# MinGo_V4_0.net
KiCad netlist of a schematic drawn in Altium Designer
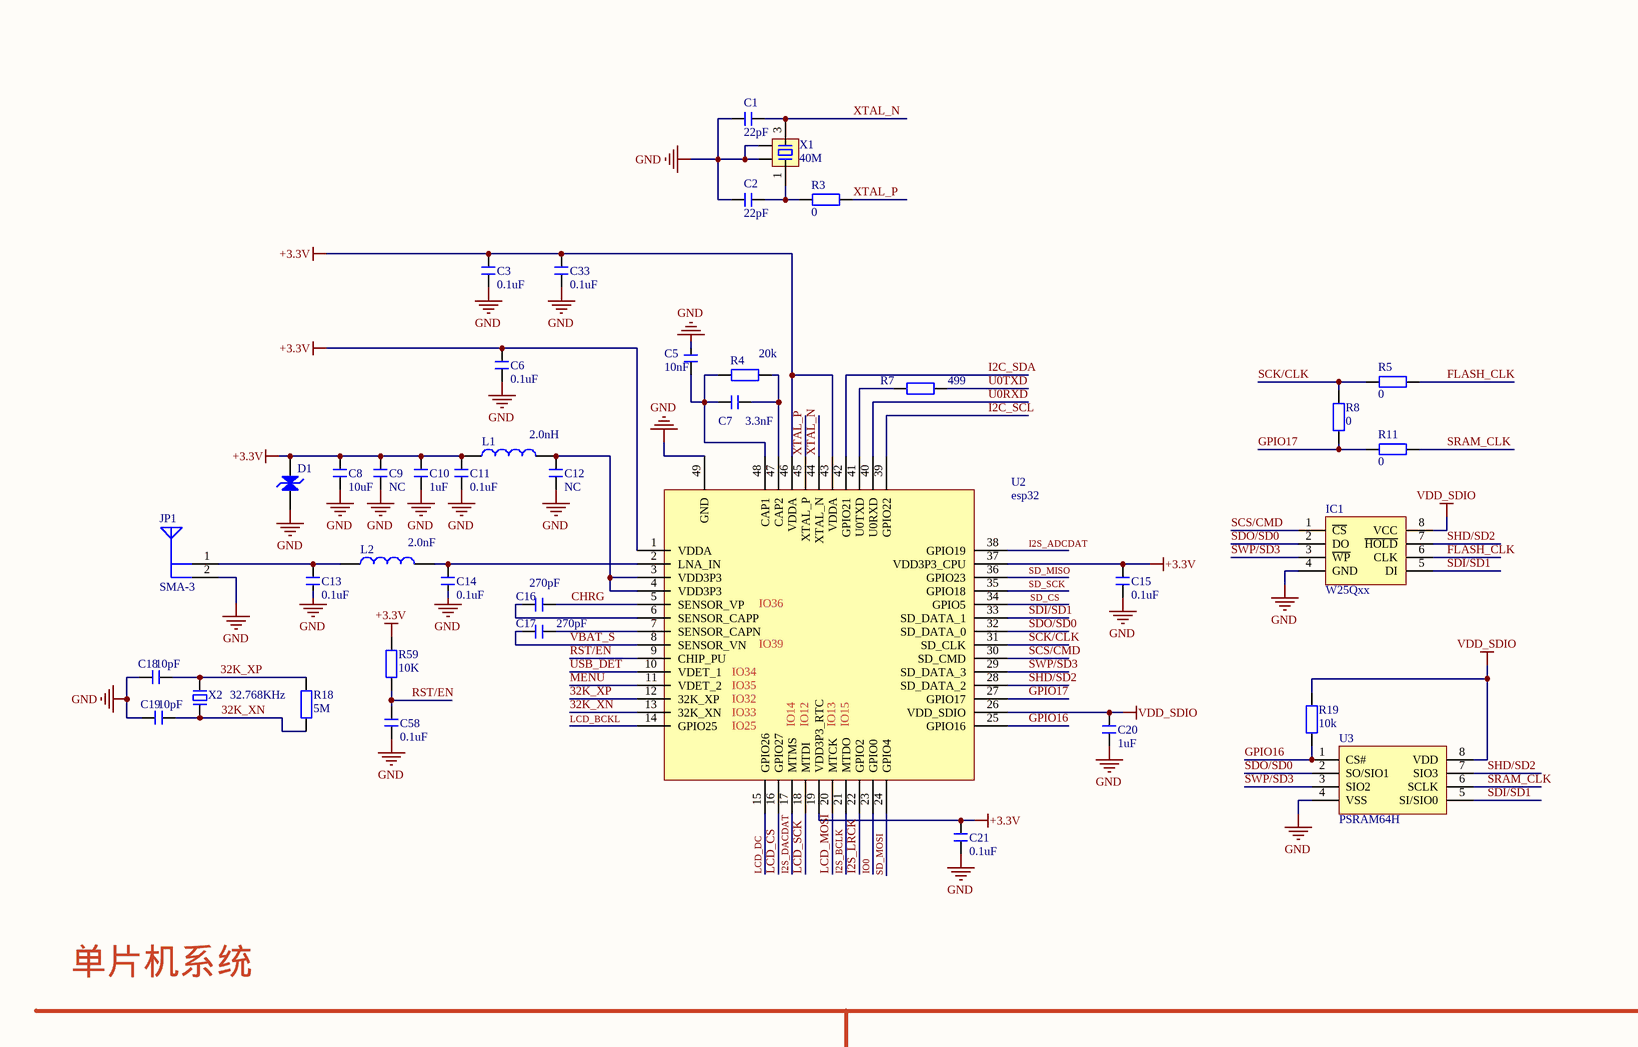
[diagram p0: MinGo_V4.0.SchDoc, top left]
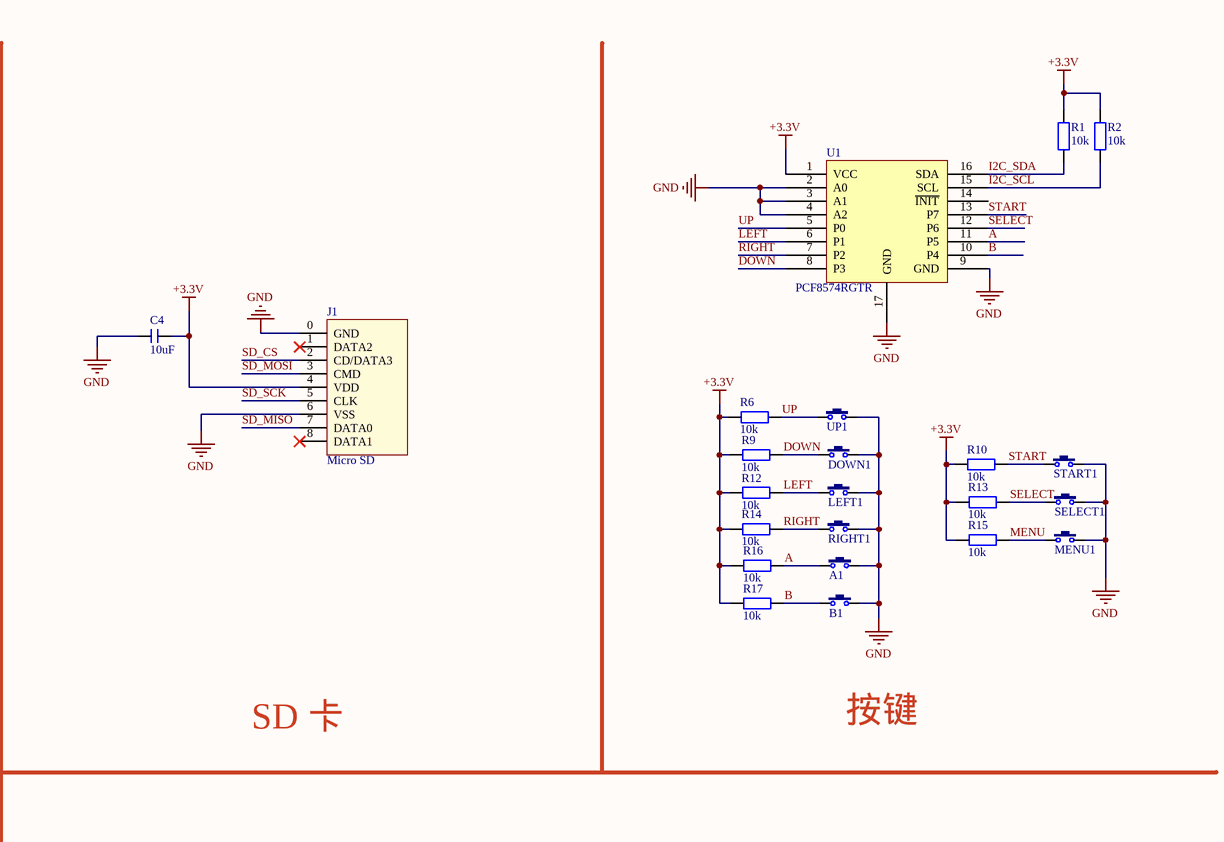
[diagram p1: MinGo_V4.0.SchDoc, top right]
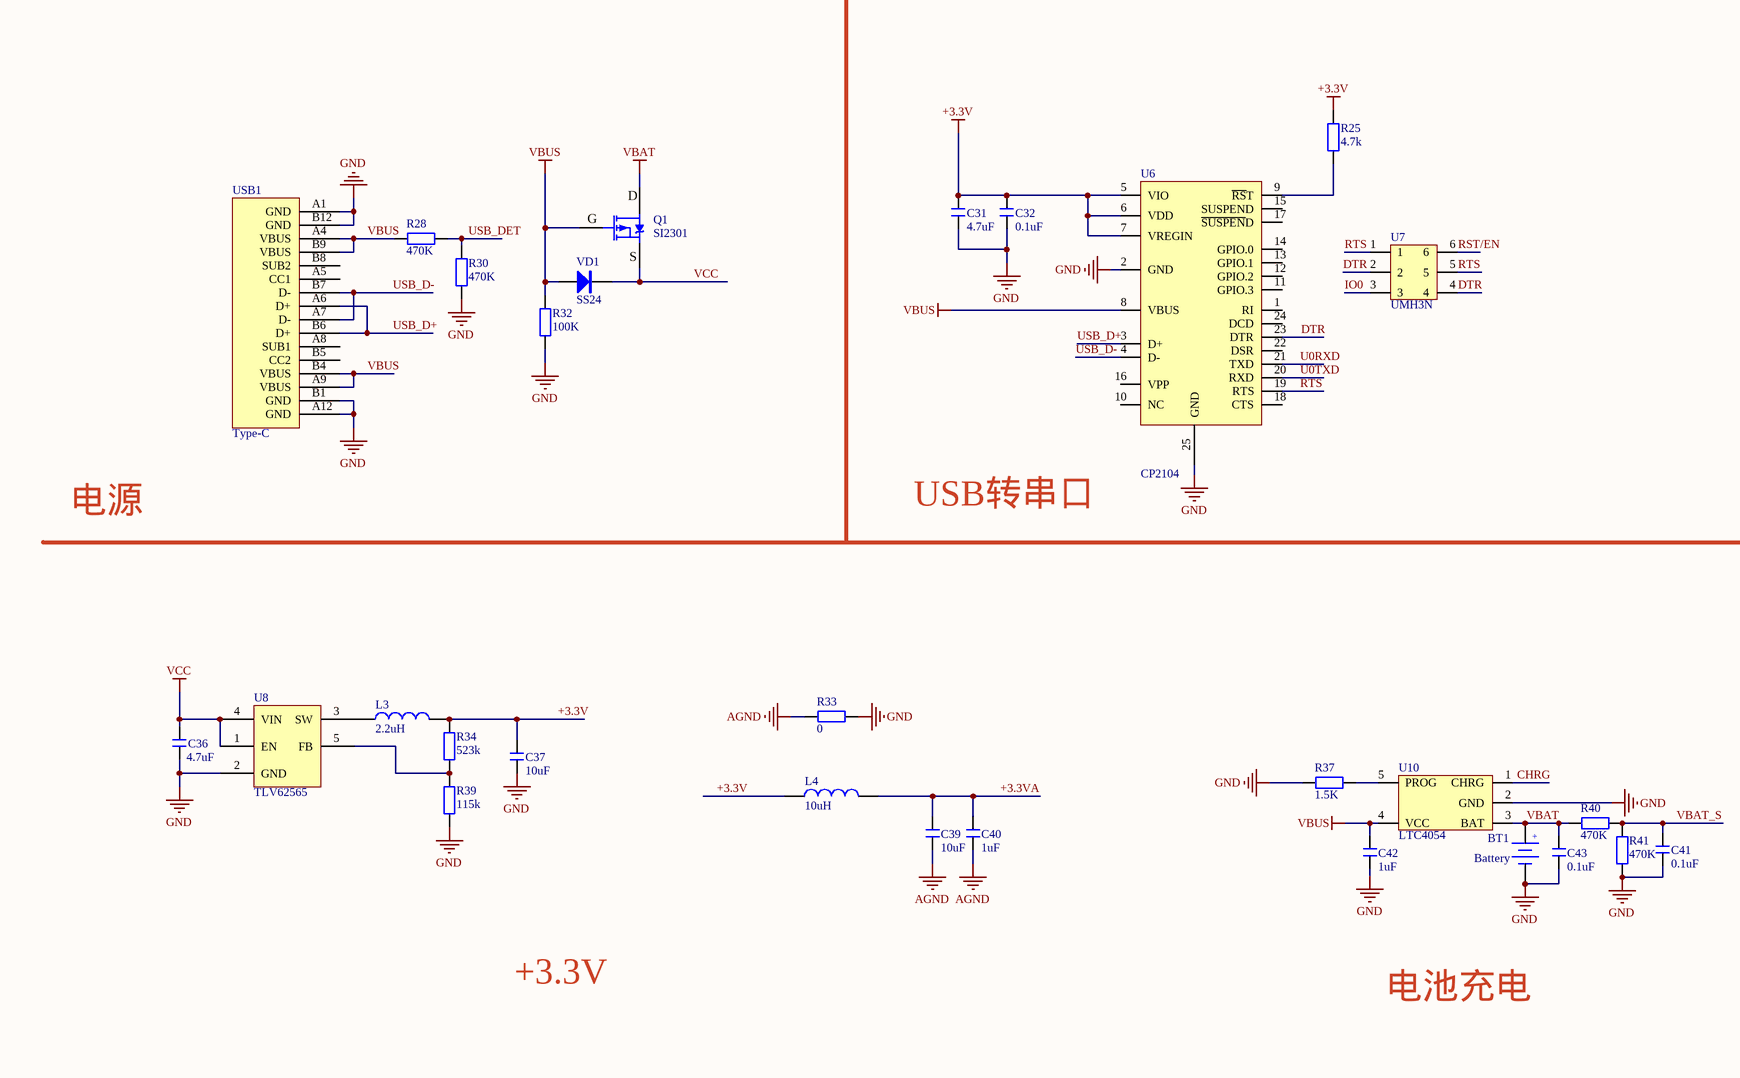
[diagram p2: MinGo_V4.0.SchDoc, bottom left]
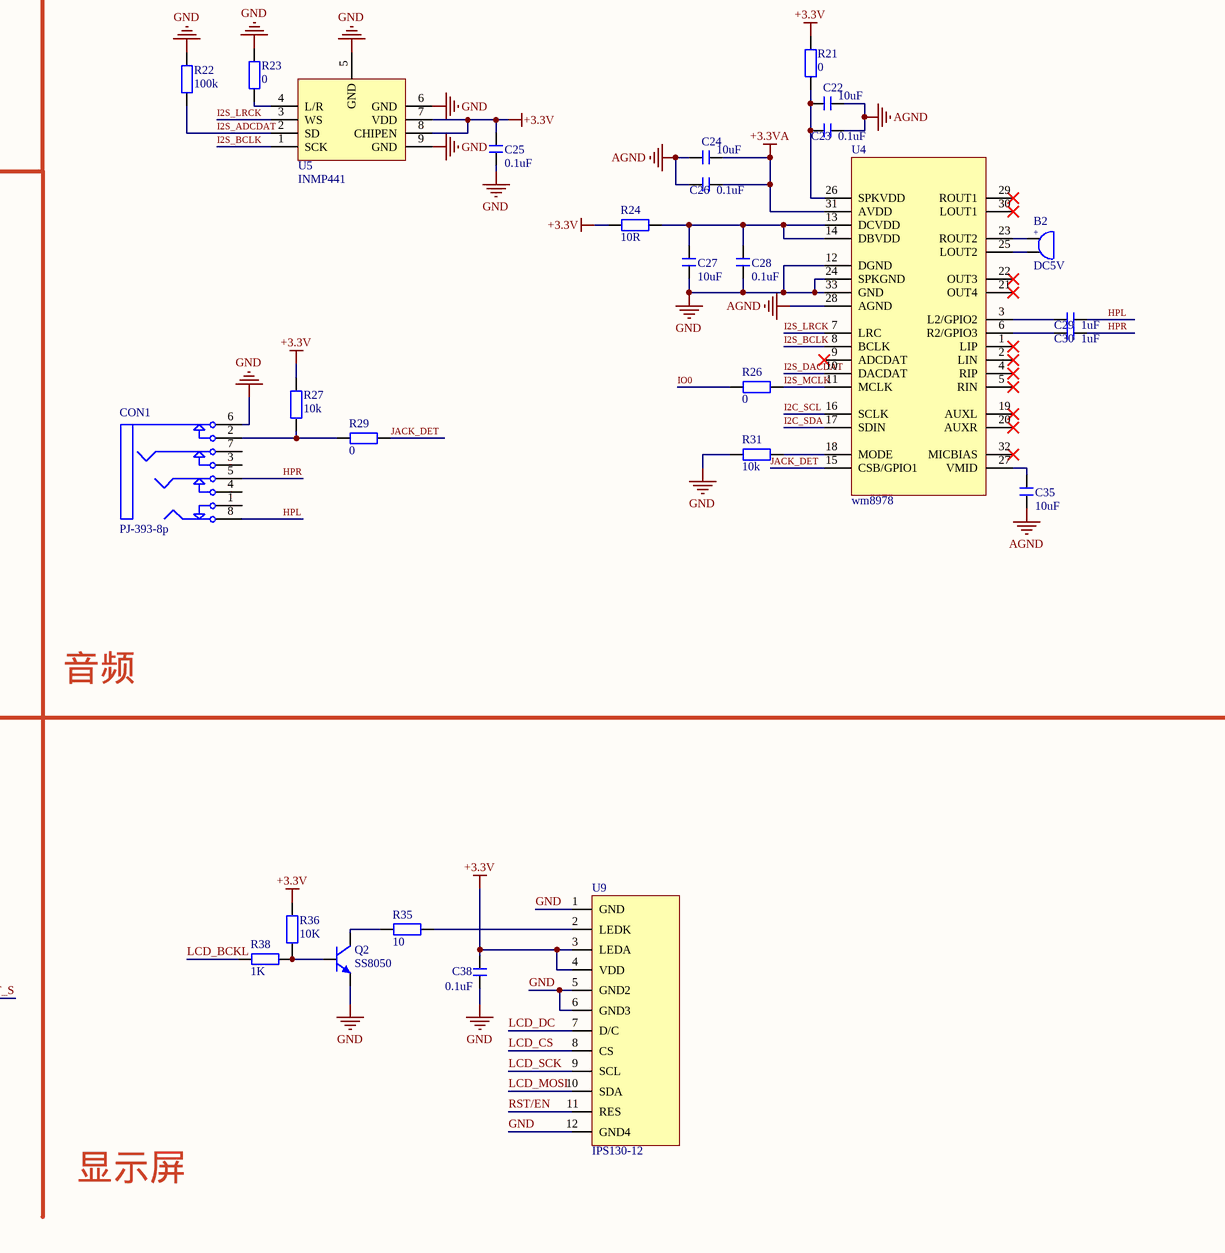
[diagram p3: MinGo_V4.0.SchDoc, bottom right]

(export (version "E")
  (design (tool "Eeschema 10.0.6"))
  (components
    (comp (ref "A1")
      (value "SW SMD-2")
      (footprint "Touch key 3")
      (description "Arduboy 用")
      (libsource (lib "按键-开关") (part "SW SMD-2"))
    )
    (comp (ref "B1")
      (value "SW SMD-2")
      (footprint "Touch key 3")
      (description "Arduboy 用")
      (libsource (lib "按键-开关") (part "SW SMD-2"))
    )
    (comp (ref "B2")
      (value "DC5V")
      (footprint "BEEP SMD-2")
      (description "蜂鸣器")
      (fields (field (name "版权归属") "黎明电子style"))
      (libsource (lib "未分类器件") (part "BEEP"))
    )
    (comp (ref "BT1")
      (value "Battery")
      (footprint "Li-Bettery SMD")
      (description "锂电池")
      (libsource (lib "未分类器件") (part "Battery"))
    )
    (comp (ref "C1")
      (value "22pF")
      (footprint "C 0402")
      (description "无极性贴片电容")
      (fields (field (name "版权归属") "黎明电子style"))
      (libsource (lib "电阻-电容-电感") (part "C"))
    )
    (comp (ref "C2")
      (value "22pF")
      (footprint "C 0402")
      (description "无极性贴片电容")
      (fields (field (name "版权归属") "黎明电子style"))
      (libsource (lib "电阻-电容-电感") (part "C"))
    )
    (comp (ref "C3")
      (value "0.1uF")
      (footprint "C 0402")
      (description "无极性贴片电容")
      (fields (field (name "版权归属") "黎明电子style"))
      (libsource (lib "电阻-电容-电感") (part "C"))
    )
    (comp (ref "C4")
      (value "10uF")
      (footprint "C 0603")
      (description "无极性贴片电容")
      (fields (field (name "版权归属") "黎明电子style"))
      (libsource (lib "电阻-电容-电感") (part "C"))
    )
    (comp (ref "C5")
      (value "10nF")
      (footprint "C 0402")
      (description "无极性贴片电容")
      (fields (field (name "版权归属") "黎明电子style"))
      (libsource (lib "电阻-电容-电感") (part "C"))
    )
    (comp (ref "C6")
      (value "0.1uF")
      (footprint "C 0402")
      (description "无极性贴片电容")
      (fields (field (name "版权归属") "黎明电子style"))
      (libsource (lib "电阻-电容-电感") (part "C"))
    )
    (comp (ref "C7")
      (value "3.3nF")
      (footprint "C 0402")
      (description "无极性贴片电容")
      (fields (field (name "版权归属") "黎明电子style"))
      (libsource (lib "电阻-电容-电感") (part "C"))
    )
    (comp (ref "C8")
      (value "10uF")
      (footprint "C 0603")
      (description "无极性贴片电容")
      (fields (field (name "版权归属") "黎明电子style"))
      (libsource (lib "电阻-电容-电感") (part "C"))
    )
    (comp (ref "C9")
      (value "NC")
      (footprint "C 0402")
      (description "无极性贴片电容")
      (fields (field (name "版权归属") "黎明电子style"))
      (libsource (lib "电阻-电容-电感") (part "C"))
    )
    (comp (ref "C10")
      (value "1uF")
      (footprint "C 0402")
      (description "无极性贴片电容")
      (fields (field (name "版权归属") "黎明电子style"))
      (libsource (lib "电阻-电容-电感") (part "C"))
    )
    (comp (ref "C11")
      (value "0.1uF")
      (footprint "C 0402")
      (description "无极性贴片电容")
      (fields (field (name "版权归属") "黎明电子style"))
      (libsource (lib "电阻-电容-电感") (part "C"))
    )
    (comp (ref "C12")
      (value "NC")
      (footprint "C 0402")
      (description "无极性贴片电容")
      (fields (field (name "版权归属") "黎明电子style"))
      (libsource (lib "电阻-电容-电感") (part "C"))
    )
    (comp (ref "C13")
      (value "0.1uF")
      (footprint "C 0402")
      (description "无极性贴片电容")
      (fields (field (name "版权归属") "黎明电子style"))
      (libsource (lib "电阻-电容-电感") (part "C"))
    )
    (comp (ref "C14")
      (value "0.1uF")
      (footprint "C 0402")
      (description "无极性贴片电容")
      (fields (field (name "版权归属") "黎明电子style"))
      (libsource (lib "电阻-电容-电感") (part "C"))
    )
    (comp (ref "C15")
      (value "0.1uF")
      (footprint "C 0402")
      (description "无极性贴片电容")
      (fields (field (name "版权归属") "黎明电子style"))
      (libsource (lib "电阻-电容-电感") (part "C"))
    )
    (comp (ref "C16")
      (value "270pF")
      (footprint "C 0402")
      (description "无极性贴片电容")
      (fields (field (name "版权归属") "黎明电子style"))
      (libsource (lib "电阻-电容-电感") (part "C"))
    )
    (comp (ref "C17")
      (value "270pF")
      (footprint "C 0402")
      (description "无极性贴片电容")
      (fields (field (name "版权归属") "黎明电子style"))
      (libsource (lib "电阻-电容-电感") (part "C"))
    )
    (comp (ref "C18")
      (value "10pF")
      (footprint "C 0402")
      (description "无极性贴片电容")
      (fields (field (name "版权归属") "黎明电子style"))
      (libsource (lib "电阻-电容-电感") (part "C"))
    )
    (comp (ref "C19")
      (value "10pF")
      (footprint "C 0402")
      (description "无极性贴片电容")
      (fields (field (name "版权归属") "黎明电子style"))
      (libsource (lib "电阻-电容-电感") (part "C"))
    )
    (comp (ref "C20")
      (value "1uF")
      (footprint "C 0402")
      (description "无极性贴片电容")
      (fields (field (name "版权归属") "黎明电子style"))
      (libsource (lib "电阻-电容-电感") (part "C"))
    )
    (comp (ref "C21")
      (value "0.1uF")
      (footprint "C 0402")
      (description "无极性贴片电容")
      (fields (field (name "版权归属") "黎明电子style"))
      (libsource (lib "电阻-电容-电感") (part "C"))
    )
    (comp (ref "C22")
      (value "10uF")
      (footprint "C 0603")
      (description "无极性贴片电容")
      (fields (field (name "版权归属") "黎明电子style"))
      (libsource (lib "电阻-电容-电感") (part "C"))
    )
    (comp (ref "C23")
      (value "0.1uF")
      (footprint "C 0402")
      (description "无极性贴片电容")
      (fields (field (name "版权归属") "黎明电子style"))
      (libsource (lib "电阻-电容-电感") (part "C"))
    )
    (comp (ref "C24")
      (value "10uF")
      (footprint "C 0603")
      (description "无极性贴片电容")
      (fields (field (name "版权归属") "黎明电子style"))
      (libsource (lib "电阻-电容-电感") (part "C"))
    )
    (comp (ref "C25")
      (value "0.1uF")
      (footprint "C 0402")
      (description "无极性贴片电容")
      (fields (field (name "版权归属") "黎明电子style"))
      (libsource (lib "电阻-电容-电感") (part "C"))
    )
    (comp (ref "C26")
      (value "0.1uF")
      (footprint "C 0402")
      (description "无极性贴片电容")
      (fields (field (name "版权归属") "黎明电子style"))
      (libsource (lib "电阻-电容-电感") (part "C"))
    )
    (comp (ref "C27")
      (value "10uF")
      (footprint "C 0603")
      (description "无极性贴片电容")
      (fields (field (name "版权归属") "黎明电子style"))
      (libsource (lib "电阻-电容-电感") (part "C"))
    )
    (comp (ref "C28")
      (value "0.1uF")
      (footprint "C 0402")
      (description "无极性贴片电容")
      (fields (field (name "版权归属") "黎明电子style"))
      (libsource (lib "电阻-电容-电感") (part "C"))
    )
    (comp (ref "C29")
      (value "1uF")
      (footprint "C 0603")
      (description "无极性贴片电容")
      (fields (field (name "版权归属") "黎明电子style"))
      (libsource (lib "电阻-电容-电感") (part "C"))
    )
    (comp (ref "C30")
      (value "1uF")
      (footprint "C 0603")
      (description "无极性贴片电容")
      (fields (field (name "版权归属") "黎明电子style"))
      (libsource (lib "电阻-电容-电感") (part "C"))
    )
    (comp (ref "C31")
      (value "4.7uF")
      (footprint "C 0603")
      (description "无极性贴片电容")
      (fields (field (name "版权归属") "黎明电子style"))
      (libsource (lib "电阻-电容-电感") (part "C"))
    )
    (comp (ref "C32")
      (value "0.1uF")
      (footprint "C 0402")
      (description "无极性贴片电容")
      (fields (field (name "版权归属") "黎明电子style"))
      (libsource (lib "电阻-电容-电感") (part "C"))
    )
    (comp (ref "C33")
      (value "0.1uF")
      (footprint "C 0402")
      (description "无极性贴片电容")
      (fields (field (name "版权归属") "黎明电子style"))
      (libsource (lib "电阻-电容-电感") (part "C"))
    )
    (comp (ref "C35")
      (value "10uF")
      (footprint "C 0603")
      (description "无极性贴片电容")
      (fields (field (name "版权归属") "黎明电子style"))
      (libsource (lib "电阻-电容-电感") (part "C"))
    )
    (comp (ref "C36")
      (value "4.7uF")
      (footprint "C 0805")
      (description "无极性贴片电容")
      (fields (field (name "版权归属") "黎明电子style"))
      (libsource (lib "电阻-电容-电感") (part "C"))
    )
    (comp (ref "C37")
      (value "10uF")
      (footprint "C 0805")
      (description "无极性贴片电容")
      (fields (field (name "版权归属") "黎明电子style"))
      (libsource (lib "电阻-电容-电感") (part "C"))
    )
    (comp (ref "C38")
      (value "0.1uF")
      (footprint "C 0402")
      (description "无极性贴片电容")
      (fields (field (name "版权归属") "黎明电子style"))
      (libsource (lib "电阻-电容-电感") (part "C"))
    )
    (comp (ref "C39")
      (value "10uF")
      (footprint "C 0603")
      (description "无极性贴片电容")
      (fields (field (name "版权归属") "黎明电子style"))
      (libsource (lib "电阻-电容-电感") (part "C"))
    )
    (comp (ref "C40")
      (value "1uF")
      (footprint "C 0603")
      (description "无极性贴片电容")
      (fields (field (name "版权归属") "黎明电子style"))
      (libsource (lib "电阻-电容-电感") (part "C"))
    )
    (comp (ref "C41")
      (value "0.1uF")
      (footprint "C 0402")
      (description "无极性贴片电容")
      (fields (field (name "版权归属") "黎明电子style"))
      (libsource (lib "电阻-电容-电感") (part "C"))
    )
    (comp (ref "C42")
      (value "1uF")
      (footprint "C 0603")
      (description "无极性贴片电容")
      (fields (field (name "版权归属") "黎明电子style"))
      (libsource (lib "电阻-电容-电感") (part "C"))
    )
    (comp (ref "C43")
      (value "0.1uF")
      (footprint "C 0402")
      (description "无极性贴片电容")
      (fields (field (name "版权归属") "黎明电子style"))
      (libsource (lib "电阻-电容-电感") (part "C"))
    )
    (comp (ref "C58")
      (value "0.1uF")
      (footprint "C 0603")
      (description "无极性贴片电容")
      (fields (field (name "版权归属") "黎明电子style"))
      (libsource (lib "电阻-电容-电感") (part "C"))
    )
    (comp (ref "CON1") (value "PJ-393-8p") (footprint "PJ393-8p") (libsource (lib "接口类") (part "PJ-393-8p")))
    (comp (ref "D1")
      (value "~")
      (footprint "SOD-323")
      (description "瞬态电压抑制二极管")
      (fields (field (name "版权归属") "黎明电子style"))
      (libsource (lib "二极管-整流桥") (part "DR"))
    )
    (comp (ref "DOWN1")
      (value "SW SMD-2")
      (footprint "Touch key 3")
      (description "Arduboy 用")
      (libsource (lib "按键-开关") (part "SW SMD-2"))
    )
    (comp (ref "IC1")
      (value "W25Qxx")
      (footprint "SOP8W_N")
      (description "外置Flash")
      (fields (field (name "版权归属") "黎明电子style"))
      (libsource (lib "IC芯片") (part "W25Qxx"))
    )
    (comp (ref "J1")
      (value "Micro SD")
      (footprint "MY SD CARD")
      (description "Micro SD卡")
      (fields (field (name "版权归属") "黎明电子style"))
      (libsource (lib "接口类") (part "Micro SD"))
    )
    (comp (ref "JP1")
      (value "SMA-3")
      (footprint "2.4GANTS10")
      (description "SMA-板载2.4G射频天线")
      (fields (field (name "版权归属") "黎明电子style"))
      (libsource (lib "接口类") (part "SMA-3"))
    )
    (comp (ref "L1")
      (value "2.0nH")
      (footprint "L 0402")
      (description "小功率贴片电感")
      (fields (field (name "版权归属") "黎明电子style"))
      (libsource (lib "电阻-电容-电感") (part "L"))
    )
    (comp (ref "L2")
      (value "2.0nF")
      (footprint "L 0402")
      (description "小功率贴片电感")
      (fields (field (name "版权归属") "黎明电子style"))
      (libsource (lib "电阻-电容-电感") (part "L"))
    )
    (comp (ref "L3")
      (value "2.2uH")
      (footprint "3015")
      (description "小功率贴片电感")
      (fields (field (name "版权归属") "黎明电子style"))
      (libsource (lib "电阻-电容-电感") (part "L"))
    )
    (comp (ref "L4")
      (value "10uH")
      (footprint "L 1206")
      (description "小功率贴片电感")
      (fields (field (name "版权归属") "黎明电子style"))
      (libsource (lib "电阻-电容-电感") (part "L"))
    )
    (comp (ref "LEFT1")
      (value "SW SMD-2")
      (footprint "Touch key 3")
      (description "Arduboy 用")
      (libsource (lib "按键-开关") (part "SW SMD-2"))
    )
    (comp (ref "MENU1")
      (value "SW SMD-2")
      (footprint "SW SMD-4.8*4.8*0.5")
      (description "Arduboy 用")
      (libsource (lib "按键-开关") (part "SW SMD-2"))
    )
    (comp (ref "Q1")
      (value "SI2301")
      (footprint "SOT23-3N")
      (description "P沟道场效应管")
      (fields (field (name "版权归属") "黎明电子style"))
      (libsource (lib "场效应管-可控硅") (part "SI2301"))
    )
    (comp (ref "Q2")
      (value "SS8050")
      (footprint "SOT23-3M")
      (description "高频放大-NPN型")
      (fields (field (name "版权归属") "黎明电子style"))
      (libsource (lib "三极管") (part "8050-SMD"))
    )
    (comp (ref "R1")
      (value "10k")
      (footprint "R 0402")
      (description "贴片电阻")
      (fields (field (name "版权归属") "黎明电子style"))
      (libsource (lib "电阻-电容-电感") (part "R"))
    )
    (comp (ref "R2")
      (value "10k")
      (footprint "R 0402")
      (description "贴片电阻")
      (fields (field (name "版权归属") "黎明电子style"))
      (libsource (lib "电阻-电容-电感") (part "R"))
    )
    (comp (ref "R3")
      (value "0")
      (footprint "R 0402")
      (description "贴片电阻")
      (fields (field (name "版权归属") "黎明电子style"))
      (libsource (lib "电阻-电容-电感") (part "R"))
    )
    (comp (ref "R4")
      (value "20k")
      (footprint "R 0402")
      (description "贴片电阻")
      (fields (field (name "版权归属") "黎明电子style"))
      (libsource (lib "电阻-电容-电感") (part "R"))
    )
    (comp (ref "R5")
      (value "0")
      (footprint "R 0402")
      (description "贴片电阻")
      (fields (field (name "版权归属") "黎明电子style"))
      (libsource (lib "电阻-电容-电感") (part "R"))
    )
    (comp (ref "R6")
      (value "10k")
      (footprint "R 0402")
      (description "贴片电阻")
      (fields (field (name "版权归属") "黎明电子style"))
      (libsource (lib "电阻-电容-电感") (part "R"))
    )
    (comp (ref "R7")
      (value "499")
      (footprint "R 0402")
      (description "贴片电阻")
      (fields (field (name "版权归属") "黎明电子style"))
      (libsource (lib "电阻-电容-电感") (part "R"))
    )
    (comp (ref "R8")
      (value "0")
      (footprint "R 0402")
      (description "贴片电阻")
      (fields (field (name "版权归属") "黎明电子style"))
      (libsource (lib "电阻-电容-电感") (part "R"))
    )
    (comp (ref "R9")
      (value "10k")
      (footprint "R 0402")
      (description "贴片电阻")
      (fields (field (name "版权归属") "黎明电子style"))
      (libsource (lib "电阻-电容-电感") (part "R"))
    )
    (comp (ref "R10")
      (value "10k")
      (footprint "R 0402")
      (description "贴片电阻")
      (fields (field (name "版权归属") "黎明电子style"))
      (libsource (lib "电阻-电容-电感") (part "R"))
    )
    (comp (ref "R11")
      (value "0")
      (footprint "R 0402")
      (description "贴片电阻")
      (fields (field (name "版权归属") "黎明电子style"))
      (libsource (lib "电阻-电容-电感") (part "R"))
    )
    (comp (ref "R12")
      (value "10k")
      (footprint "R 0402")
      (description "贴片电阻")
      (fields (field (name "版权归属") "黎明电子style"))
      (libsource (lib "电阻-电容-电感") (part "R"))
    )
    (comp (ref "R13")
      (value "10k")
      (footprint "R 0402")
      (description "贴片电阻")
      (fields (field (name "版权归属") "黎明电子style"))
      (libsource (lib "电阻-电容-电感") (part "R"))
    )
    (comp (ref "R14")
      (value "10k")
      (footprint "R 0402")
      (description "贴片电阻")
      (fields (field (name "版权归属") "黎明电子style"))
      (libsource (lib "电阻-电容-电感") (part "R"))
    )
    (comp (ref "R15")
      (value "10k")
      (footprint "R 0402")
      (description "贴片电阻")
      (fields (field (name "版权归属") "黎明电子style"))
      (libsource (lib "电阻-电容-电感") (part "R"))
    )
    (comp (ref "R16")
      (value "10k")
      (footprint "R 0402")
      (description "贴片电阻")
      (fields (field (name "版权归属") "黎明电子style"))
      (libsource (lib "电阻-电容-电感") (part "R"))
    )
    (comp (ref "R17")
      (value "10k")
      (footprint "R 0402")
      (description "贴片电阻")
      (fields (field (name "版权归属") "黎明电子style"))
      (libsource (lib "电阻-电容-电感") (part "R"))
    )
    (comp (ref "R18")
      (value "5M")
      (footprint "R 0402")
      (description "贴片电阻")
      (fields (field (name "版权归属") "黎明电子style"))
      (libsource (lib "电阻-电容-电感") (part "R"))
    )
    (comp (ref "R19")
      (value "10k")
      (footprint "R 0402")
      (description "贴片电阻")
      (fields (field (name "版权归属") "黎明电子style"))
      (libsource (lib "电阻-电容-电感") (part "R"))
    )
    (comp (ref "R21")
      (value "0")
      (footprint "R 0603")
      (description "贴片电阻")
      (fields (field (name "版权归属") "黎明电子style"))
      (libsource (lib "电阻-电容-电感") (part "R"))
    )
    (comp (ref "R22")
      (value "100k")
      (footprint "R 0402")
      (description "贴片电阻")
      (fields (field (name "版权归属") "黎明电子style"))
      (libsource (lib "电阻-电容-电感") (part "R"))
    )
    (comp (ref "R23")
      (value "0")
      (footprint "R 0402")
      (description "贴片电阻")
      (fields (field (name "版权归属") "黎明电子style"))
      (libsource (lib "电阻-电容-电感") (part "R"))
    )
    (comp (ref "R24")
      (value "10R")
      (footprint "R 0603")
      (description "贴片电阻")
      (fields (field (name "版权归属") "黎明电子style"))
      (libsource (lib "电阻-电容-电感") (part "R"))
    )
    (comp (ref "R25")
      (value "4.7k")
      (footprint "R 0402")
      (description "贴片电阻")
      (fields (field (name "版权归属") "黎明电子style"))
      (libsource (lib "电阻-电容-电感") (part "R"))
    )
    (comp (ref "R26")
      (value "0")
      (footprint "R 0402")
      (description "贴片电阻")
      (fields (field (name "版权归属") "黎明电子style"))
      (libsource (lib "电阻-电容-电感") (part "R"))
    )
    (comp (ref "R27")
      (value "10k")
      (footprint "R 0402")
      (description "贴片电阻")
      (fields (field (name "版权归属") "黎明电子style"))
      (libsource (lib "电阻-电容-电感") (part "R"))
    )
    (comp (ref "R28")
      (value "470K")
      (footprint "R 0603")
      (description "贴片电阻")
      (fields (field (name "版权归属") "黎明电子style"))
      (libsource (lib "电阻-电容-电感") (part "R"))
    )
    (comp (ref "R29")
      (value "0")
      (footprint "R 0402")
      (description "贴片电阻")
      (fields (field (name "版权归属") "黎明电子style"))
      (libsource (lib "电阻-电容-电感") (part "R"))
    )
    (comp (ref "R30")
      (value "470K")
      (footprint "R 0603")
      (description "贴片电阻")
      (fields (field (name "版权归属") "黎明电子style"))
      (libsource (lib "电阻-电容-电感") (part "R"))
    )
    (comp (ref "R31")
      (value "10k")
      (footprint "R 0402")
      (description "贴片电阻")
      (fields (field (name "版权归属") "黎明电子style"))
      (libsource (lib "电阻-电容-电感") (part "R"))
    )
    (comp (ref "R32")
      (value "100K")
      (footprint "R 0402")
      (description "贴片电阻")
      (fields (field (name "版权归属") "黎明电子style"))
      (libsource (lib "电阻-电容-电感") (part "R"))
    )
    (comp (ref "R33")
      (value "0")
      (footprint "R 0603")
      (description "贴片电阻")
      (fields (field (name "版权归属") "黎明电子style"))
      (libsource (lib "电阻-电容-电感") (part "R"))
    )
    (comp (ref "R34")
      (value "523k")
      (footprint "R 0402")
      (description "贴片电阻")
      (fields (field (name "版权归属") "黎明电子style"))
      (libsource (lib "电阻-电容-电感") (part "R"))
    )
    (comp (ref "R35")
      (value "10")
      (footprint "R 0402")
      (description "贴片电阻")
      (fields (field (name "版权归属") "黎明电子style"))
      (libsource (lib "电阻-电容-电感") (part "R"))
    )
    (comp (ref "R36")
      (value "10K")
      (footprint "R 0402")
      (description "贴片电阻")
      (fields (field (name "版权归属") "黎明电子style"))
      (libsource (lib "电阻-电容-电感") (part "R"))
    )
    (comp (ref "R37")
      (value "1.5K")
      (footprint "R 0402")
      (description "贴片电阻")
      (fields (field (name "版权归属") "黎明电子style"))
      (libsource (lib "电阻-电容-电感") (part "R"))
    )
    (comp (ref "R38")
      (value "1K")
      (footprint "R 0402")
      (description "贴片电阻")
      (fields (field (name "版权归属") "黎明电子style"))
      (libsource (lib "电阻-电容-电感") (part "R"))
    )
    (comp (ref "R39")
      (value "115k")
      (footprint "R 0402")
      (description "贴片电阻")
      (fields (field (name "版权归属") "黎明电子style"))
      (libsource (lib "电阻-电容-电感") (part "R"))
    )
    (comp (ref "R40")
      (value "470K")
      (footprint "R 0402")
      (description "贴片电阻")
      (fields (field (name "版权归属") "黎明电子style"))
      (libsource (lib "电阻-电容-电感") (part "R"))
    )
    (comp (ref "R41")
      (value "470K")
      (footprint "R 0402")
      (description "贴片电阻")
      (fields (field (name "版权归属") "黎明电子style"))
      (libsource (lib "电阻-电容-电感") (part "R"))
    )
    (comp (ref "R59")
      (value "10K")
      (footprint "R 0402")
      (description "贴片电阻")
      (fields (field (name "版权归属") "黎明电子style"))
      (libsource (lib "电阻-电容-电感") (part "R"))
    )
    (comp (ref "RIGHT1")
      (value "SW SMD-2")
      (footprint "Touch key 3")
      (description "Arduboy 用")
      (libsource (lib "按键-开关") (part "SW SMD-2"))
    )
    (comp (ref "SELECT1")
      (value "SW SMD-2")
      (footprint "SW SMD-4.8*4.8*0.5")
      (description "Arduboy 用")
      (libsource (lib "按键-开关") (part "SW SMD-2"))
    )
    (comp (ref "START1")
      (value "SW SMD-2")
      (footprint "SW SMD-4.8*4.8*0.5")
      (description "Arduboy 用")
      (libsource (lib "按键-开关") (part "SW SMD-2"))
    )
    (comp (ref "U1")
      (value "PCF8574RGTR")
      (footprint "QFN16")
      (description "TI 8位 IO扩展芯片")
      (libsource (lib "IC芯片") (part "PCF8574RGTR"))
    )
    (comp (ref "U2")
      (value "esp32")
      (footprint "QFN48A")
      (description "esp32 芯片")
      (libsource (lib "IC芯片") (part "esp32"))
    )
    (comp (ref "U3")
      (value "PSRAM64H")
      (footprint "SOIC8")
      (description "PSRAM")
      (libsource (lib "IC芯片") (part "PSRAM64H"))
    )
    (comp (ref "U4") (value "wm8978") (footprint "QFN32 5x5_M") (libsource (lib "IC芯片") (part "wm8978")))
    (comp (ref "U5") (value "INMP441") (footprint "INMP441") (libsource (lib "IC芯片") (part "INMP441")))
    (comp (ref "U6")
      (value "CP2104")
      (footprint "QFN24")
      (description "USB转串口芯片")
      (libsource (lib "IC芯片") (part "CP2104"))
    )
    (comp (ref "U7")
      (value "UMH3N")
      (footprint "SOT336")
      (description "三极管(阵列)，内置电阻，自动下载电路用")
      (libsource (lib "IC芯片") (part "UMH3N"))
    )
    (comp (ref "U8")
      (value "TLV62565")
      (footprint "SOT23-5N")
      (description "TI TLV62565DBVR 电源管理芯片")
      (libsource (lib "IC芯片") (part "TLV62565"))
    )
    (comp (ref "U9") (value "IPS130-12") (footprint "ips154") (libsource (lib "显示器件") (part "IPS130-12")))
    (comp (ref "U10")
      (value "LTC4054")
      (footprint "SOT23-5M")
      (description "充电管理")
      (libsource (lib "IC芯片") (part "LTC4054"))
    )
    (comp (ref "UP1")
      (value "SW SMD-2")
      (footprint "Touch key 3")
      (description "Arduboy 用")
      (libsource (lib "按键-开关") (part "SW SMD-2"))
    )
    (comp (ref "USB1")
      (value "Type-C")
      (footprint "type C 16p")
      (description "USB 3.1  单排16PIN四脚插板(L=7.35) 一体式MD")
      (libsource (lib "接口类") (part "Type-C Socket"))
    )
    (comp (ref "VD1")
      (value "SS24")
      (footprint "SOD-123")
      (description "肖特基二极管")
      (fields (field (name "版权归属") "黎明电子style"))
      (libsource (lib "二极管-整流桥") (part "SS24"))
    )
    (comp (ref "X1")
      (value "40M")
      (footprint "XTAL-3225")
      (description "4脚晶振")
      (fields (field (name "版权归属") "黎明电子style"))
      (libsource (lib "保险丝-晶振") (part "XTAL-4"))
    )
    (comp (ref "X2")
      (value "32.768KHz")
      (footprint "XTAL-3215")
      (description "2脚晶振")
      (fields (field (name "版权归属") "黎明电子style"))
      (libsource (lib "保险丝-晶振") (part "XTAL-2"))
    )
  )
  (nets
    (net (code "1") (name "+3.3V") (class "Default")
      (node (ref "C10") (pin "2") (pinfunction "2_2") (pintype "passive"))
      (node (ref "C11") (pin "2") (pinfunction "2_2") (pintype "passive"))
      (node (ref "C15") (pin "2") (pinfunction "2_2") (pintype "passive"))
      (node (ref "C21") (pin "2") (pinfunction "2_2") (pintype "passive"))
      (node (ref "C25") (pin "2") (pinfunction "2_2") (pintype "passive"))
      (node (ref "C3") (pin "2") (pinfunction "2_2") (pintype "passive"))
      (node (ref "C31") (pin "2") (pinfunction "2_2") (pintype "passive"))
      (node (ref "C32") (pin "2") (pinfunction "2_2") (pintype "passive"))
      (node (ref "C33") (pin "2") (pinfunction "2_2") (pintype "passive"))
      (node (ref "C37") (pin "2") (pinfunction "2_2") (pintype "passive"))
      (node (ref "C38") (pin "2") (pinfunction "2_2") (pintype "passive"))
      (node (ref "C4") (pin "1") (pinfunction "1_1") (pintype "passive"))
      (node (ref "C6") (pin "2") (pinfunction "2_2") (pintype "passive"))
      (node (ref "C8") (pin "2") (pinfunction "2_2") (pintype "passive"))
      (node (ref "C9") (pin "2") (pinfunction "2_2") (pintype "passive"))
      (node (ref "D1") (pin "1") (pinfunction "A_1") (pintype "passive"))
      (node (ref "J1") (pin "4") (pinfunction "VDD_4") (pintype "passive"))
      (node (ref "L1") (pin "1") (pinfunction "1_1") (pintype "passive"))
      (node (ref "L3") (pin "2") (pinfunction "2_2") (pintype "passive"))
      (node (ref "L4") (pin "1") (pinfunction "1_1") (pintype "passive"))
      (node (ref "R1") (pin "1") (pinfunction "1_1") (pintype "passive"))
      (node (ref "R10") (pin "2") (pinfunction "2_2") (pintype "passive"))
      (node (ref "R12") (pin "2") (pinfunction "2_2") (pintype "passive"))
      (node (ref "R13") (pin "2") (pinfunction "2_2") (pintype "passive"))
      (node (ref "R14") (pin "2") (pinfunction "2_2") (pintype "passive"))
      (node (ref "R15") (pin "2") (pinfunction "2_2") (pintype "passive"))
      (node (ref "R16") (pin "2") (pinfunction "2_2") (pintype "passive"))
      (node (ref "R17") (pin "2") (pinfunction "2_2") (pintype "passive"))
      (node (ref "R2") (pin "1") (pinfunction "1_1") (pintype "passive"))
      (node (ref "R21") (pin "1") (pinfunction "1_1") (pintype "passive"))
      (node (ref "R24") (pin "1") (pinfunction "1_1") (pintype "passive"))
      (node (ref "R25") (pin "2") (pinfunction "2_2") (pintype "passive"))
      (node (ref "R27") (pin "1") (pinfunction "1_1") (pintype "passive"))
      (node (ref "R34") (pin "1") (pinfunction "1_1") (pintype "passive"))
      (node (ref "R36") (pin "1") (pinfunction "1_1") (pintype "passive"))
      (node (ref "R59") (pin "1") (pinfunction "1_1") (pintype "passive"))
      (node (ref "R6") (pin "2") (pinfunction "2_2") (pintype "passive"))
      (node (ref "R9") (pin "2") (pinfunction "2_2") (pintype "passive"))
      (node (ref "U1") (pin "1") (pinfunction "VCC_1") (pintype "passive"))
      (node (ref "U2") (pin "1") (pinfunction "VDDA_1") (pintype "passive"))
      (node (ref "U2") (pin "19") (pinfunction "VDD3P3_RTC_19") (pintype "passive"))
      (node (ref "U2") (pin "37") (pinfunction "VDD3P3_CPU_37") (pintype "passive"))
      (node (ref "U2") (pin "43") (pinfunction "VDDA_43") (pintype "passive"))
      (node (ref "U2") (pin "46") (pinfunction "VDDA_46") (pintype "passive"))
      (node (ref "U5") (pin "7") (pinfunction "VDD_7") (pintype "passive"))
      (node (ref "U5") (pin "8") (pinfunction "CHIPEN_8") (pintype "passive"))
      (node (ref "U6") (pin "5") (pinfunction "VIO_5") (pintype "passive"))
      (node (ref "U6") (pin "6") (pinfunction "VDD_6") (pintype "passive"))
      (node (ref "U6") (pin "7") (pinfunction "VREGIN_7") (pintype "passive"))
      (node (ref "U9") (pin "3") (pinfunction "LEDA_3") (pintype "passive"))
      (node (ref "U9") (pin "4") (pinfunction "VDD_4") (pintype "passive"))
    )
    (net (code "2") (name "+3.3VA") (class "Default")
      (node (ref "C24") (pin "2") (pinfunction "2_2") (pintype "passive"))
      (node (ref "C26") (pin "2") (pinfunction "2_2") (pintype "passive"))
      (node (ref "C39") (pin "2") (pinfunction "2_2") (pintype "passive"))
      (node (ref "C40") (pin "2") (pinfunction "2_2") (pintype "passive"))
      (node (ref "L4") (pin "2") (pinfunction "2_2") (pintype "passive"))
      (node (ref "U4") (pin "31") (pinfunction "AVDD_31") (pintype "passive"))
    )
    (net (code "3") (name "/32K_XN") (class "Default")
      (node (ref "C19") (pin "2") (pinfunction "2_2") (pintype "passive"))
      (node (ref "R18") (pin "1") (pinfunction "1_1") (pintype "passive"))
      (node (ref "U2") (pin "13") (pinfunction "32K_XN_13") (pintype "passive"))
      (node (ref "X2") (pin "1") (pinfunction "1_1") (pintype "passive"))
    )
    (net (code "4") (name "/32K_XP") (class "Default")
      (node (ref "C18") (pin "2") (pinfunction "2_2") (pintype "passive"))
      (node (ref "R18") (pin "2") (pinfunction "2_2") (pintype "passive"))
      (node (ref "U2") (pin "12") (pinfunction "32K_XP_12") (pintype "passive"))
      (node (ref "X2") (pin "2") (pinfunction "2_2") (pintype "passive"))
    )
    (net (code "5") (name "/A") (class "Default")
      (node (ref "A1") (pin "1") (pinfunction "1_1") (pintype "passive"))
      (node (ref "R16") (pin "1") (pinfunction "1_1") (pintype "passive"))
      (node (ref "U1") (pin "11") (pinfunction "P5_11") (pintype "passive"))
    )
    (net (code "6") (name "/B") (class "Default")
      (node (ref "B1") (pin "1") (pinfunction "1_1") (pintype "passive"))
      (node (ref "R17") (pin "1") (pinfunction "1_1") (pintype "passive"))
      (node (ref "U1") (pin "10") (pinfunction "P4_10") (pintype "passive"))
    )
    (net (code "7") (name "/CHRG") (class "Default")
      (node (ref "C16") (pin "1") (pinfunction "1_1") (pintype "passive"))
      (node (ref "U10") (pin "1") (pinfunction "CHRG_1") (pintype "passive"))
      (node (ref "U2") (pin "5") (pinfunction "SENSOR_VP_5") (pintype "passive"))
    )
    (net (code "8") (name "/DOWN") (class "Default")
      (node (ref "DOWN1") (pin "1") (pinfunction "1_1") (pintype "passive"))
      (node (ref "R9") (pin "1") (pinfunction "1_1") (pintype "passive"))
      (node (ref "U1") (pin "8") (pinfunction "P3_8") (pintype "passive"))
    )
    (net (code "9") (name "/DTR") (class "Default")
      (node (ref "U6") (pin "23") (pinfunction "DTR_23") (pintype "passive"))
      (node (ref "U7") (pin "2") (pinfunction "2_2") (pintype "passive"))
      (node (ref "U7") (pin "4") (pinfunction "4_4") (pintype "passive"))
    )
    (net (code "10") (name "/FLASH_CLK") (class "Default")
      (node (ref "IC1") (pin "6") (pinfunction "CLK_6") (pintype "passive"))
      (node (ref "R5") (pin "2") (pinfunction "2_2") (pintype "passive"))
    )
    (net (code "11") (name "/GPIO16") (class "Default")
      (node (ref "R19") (pin "1") (pinfunction "1_1") (pintype "passive"))
      (node (ref "U2") (pin "25") (pinfunction "GPIO16_25") (pintype "passive"))
      (node (ref "U3") (pin "1") (pinfunction "CS#_1") (pintype "passive"))
    )
    (net (code "12") (name "/GPIO17") (class "Default")
      (node (ref "R11") (pin "1") (pinfunction "1_1") (pintype "passive"))
      (node (ref "R8") (pin "1") (pinfunction "1_1") (pintype "passive"))
      (node (ref "U2") (pin "27") (pinfunction "GPIO17_27") (pintype "passive"))
    )
    (net (code "13") (name "/HPL") (class "Default")
      (node (ref "C29") (pin "2") (pinfunction "2_2") (pintype "passive"))
      (node (ref "CON1") (pin "8") (pinfunction "8_8") (pintype "passive"))
    )
    (net (code "14") (name "/HPR") (class "Default")
      (node (ref "C30") (pin "2") (pinfunction "2_2") (pintype "passive"))
      (node (ref "CON1") (pin "5") (pinfunction "5_5") (pintype "passive"))
    )
    (net (code "15") (name "/I2C_SCL") (class "Default")
      (node (ref "R2") (pin "2") (pinfunction "2_2") (pintype "passive"))
      (node (ref "U1") (pin "15") (pinfunction "SCL_15") (pintype "passive"))
      (node (ref "U2") (pin "39") (pinfunction "GPIO22_39") (pintype "passive"))
      (node (ref "U4") (pin "16") (pinfunction "SCLK_16") (pintype "passive"))
    )
    (net (code "16") (name "/I2C_SDA") (class "Default")
      (node (ref "R1") (pin "2") (pinfunction "2_2") (pintype "passive"))
      (node (ref "U1") (pin "16") (pinfunction "SDA_16") (pintype "passive"))
      (node (ref "U2") (pin "42") (pinfunction "GPIO21_42") (pintype "passive"))
      (node (ref "U4") (pin "17") (pinfunction "SDIN_17") (pintype "passive"))
    )
    (net (code "17") (name "/I2S_ADCDAT") (class "Default")
      (node (ref "R22") (pin "1") (pinfunction "1_1") (pintype "passive"))
      (node (ref "U2") (pin "38") (pinfunction "GPIO19_38") (pintype "passive"))
      (node (ref "U5") (pin "2") (pinfunction "SD_2") (pintype "passive"))
    )
    (net (code "18") (name "/I2S_BCLK") (class "Default")
      (node (ref "U2") (pin "21") (pinfunction "MTDO_21") (pintype "passive"))
      (node (ref "U4") (pin "8") (pinfunction "BCLK_8") (pintype "passive"))
      (node (ref "U5") (pin "1") (pinfunction "SCK_1") (pintype "passive"))
    )
    (net (code "19") (name "/I2S_DACDAT") (class "Default")
      (node (ref "U2") (pin "17") (pinfunction "MTMS_17") (pintype "passive"))
      (node (ref "U4") (pin "10") (pinfunction "DACDAT_10") (pintype "passive"))
    )
    (net (code "20") (name "/I2S_LRCK") (class "Default")
      (node (ref "U2") (pin "22") (pinfunction "GPIO2_22") (pintype "passive"))
      (node (ref "U4") (pin "7") (pinfunction "LRC_7") (pintype "passive"))
      (node (ref "U5") (pin "3") (pinfunction "WS_3") (pintype "passive"))
    )
    (net (code "21") (name "/I2S_MCLK") (class "Default")
      (node (ref "R26") (pin "2") (pinfunction "2_2") (pintype "passive"))
      (node (ref "U4") (pin "11") (pinfunction "MCLK_11") (pintype "passive"))
    )
    (net (code "22") (name "/IO0") (class "Default")
      (node (ref "R26") (pin "1") (pinfunction "1_1") (pintype "passive"))
      (node (ref "U2") (pin "23") (pinfunction "GPIO0_23") (pintype "passive"))
      (node (ref "U7") (pin "3") (pinfunction "3_3") (pintype "passive"))
    )
    (net (code "23") (name "/JACK_DET") (class "Default")
      (node (ref "R29") (pin "2") (pinfunction "2_2") (pintype "passive"))
      (node (ref "U4") (pin "15") (pinfunction "CSB/GPIO1_15") (pintype "passive"))
    )
    (net (code "24") (name "/LCD_BCKL") (class "Default")
      (node (ref "R38") (pin "1") (pinfunction "1_1") (pintype "passive"))
      (node (ref "U2") (pin "14") (pinfunction "GPIO25_14") (pintype "passive"))
    )
    (net (code "25") (name "/LCD_CS") (class "Default")
      (node (ref "U2") (pin "16") (pinfunction "GPIO27_16") (pintype "passive"))
      (node (ref "U9") (pin "8") (pinfunction "CS_8") (pintype "passive"))
    )
    (net (code "26") (name "/LCD_DC") (class "Default")
      (node (ref "U2") (pin "15") (pinfunction "GPIO26_15") (pintype "passive"))
      (node (ref "U9") (pin "7") (pinfunction "D/C_7") (pintype "passive"))
    )
    (net (code "27") (name "/LCD_MOSI") (class "Default")
      (node (ref "U2") (pin "20") (pinfunction "MTCK_20") (pintype "passive"))
      (node (ref "U9") (pin "10") (pinfunction "SDA_10") (pintype "passive"))
    )
    (net (code "28") (name "/LCD_SCK") (class "Default")
      (node (ref "U2") (pin "18") (pinfunction "MTDI_18") (pintype "passive"))
      (node (ref "U9") (pin "9") (pinfunction "SCL_9") (pintype "passive"))
    )
    (net (code "29") (name "/LEFT") (class "Default")
      (node (ref "LEFT1") (pin "1") (pinfunction "1_1") (pintype "passive"))
      (node (ref "R12") (pin "1") (pinfunction "1_1") (pintype "passive"))
      (node (ref "U1") (pin "6") (pinfunction "P1_6") (pintype "passive"))
    )
    (net (code "30") (name "/MENU") (class "Default")
      (node (ref "MENU1") (pin "1") (pinfunction "1_1") (pintype "passive"))
      (node (ref "R15") (pin "1") (pinfunction "1_1") (pintype "passive"))
      (node (ref "U2") (pin "11") (pinfunction "VDET_2_11") (pintype "passive"))
    )
    (net (code "31") (name "/RIGHT") (class "Default")
      (node (ref "R14") (pin "1") (pinfunction "1_1") (pintype "passive"))
      (node (ref "RIGHT1") (pin "1") (pinfunction "1_1") (pintype "passive"))
      (node (ref "U1") (pin "7") (pinfunction "P2_7") (pintype "passive"))
    )
    (net (code "32") (name "/RST{slash}EN") (class "Default")
      (node (ref "C58") (pin "2") (pinfunction "2_2") (pintype "passive"))
      (node (ref "R59") (pin "2") (pinfunction "2_2") (pintype "passive"))
      (node (ref "U2") (pin "9") (pinfunction "CHIP_PU_9") (pintype "passive"))
      (node (ref "U7") (pin "6") (pinfunction "6_6") (pintype "passive"))
      (node (ref "U9") (pin "11") (pinfunction "RES_11") (pintype "passive"))
    )
    (net (code "33") (name "/RTS") (class "Default")
      (node (ref "U6") (pin "19") (pinfunction "RTS_19") (pintype "passive"))
      (node (ref "U7") (pin "1") (pinfunction "1_1") (pintype "passive"))
      (node (ref "U7") (pin "5") (pinfunction "5_5") (pintype "passive"))
    )
    (net (code "34") (name "/SCK{slash}CLK") (class "Default")
      (node (ref "R5") (pin "1") (pinfunction "1_1") (pintype "passive"))
      (node (ref "R8") (pin "2") (pinfunction "2_2") (pintype "passive"))
      (node (ref "U2") (pin "31") (pinfunction "SD_CLK_31") (pintype "passive"))
    )
    (net (code "35") (name "/SCS{slash}CMD") (class "Default")
      (node (ref "IC1") (pin "1") (pinfunction "~{CS}_1") (pintype "passive"))
      (node (ref "U2") (pin "30") (pinfunction "SD_CMD_30") (pintype "passive"))
    )
    (net (code "36") (name "/SDI{slash}SD1") (class "Default")
      (node (ref "IC1") (pin "5") (pinfunction "DI_5") (pintype "passive"))
      (node (ref "U2") (pin "33") (pinfunction "SD_DATA_1_33") (pintype "passive"))
      (node (ref "U3") (pin "5") (pinfunction "SI/SIO0_5") (pintype "passive"))
    )
    (net (code "37") (name "/SDO{slash}SD0") (class "Default")
      (node (ref "IC1") (pin "2") (pinfunction "DO_2") (pintype "passive"))
      (node (ref "U2") (pin "32") (pinfunction "SD_DATA_0_32") (pintype "passive"))
      (node (ref "U3") (pin "2") (pinfunction "SO/SIO1_2") (pintype "passive"))
    )
    (net (code "38") (name "/SD_CS") (class "Default")
      (node (ref "J1") (pin "2") (pinfunction "CD/DATA3_2") (pintype "passive"))
      (node (ref "U2") (pin "34") (pinfunction "GPIO5_34") (pintype "passive"))
    )
    (net (code "39") (name "/SD_MISO") (class "Default")
      (node (ref "J1") (pin "7") (pinfunction "DATA0_7") (pintype "passive"))
      (node (ref "U2") (pin "36") (pinfunction "GPIO23_36") (pintype "passive"))
    )
    (net (code "40") (name "/SD_MOSI") (class "Default")
      (node (ref "J1") (pin "3") (pinfunction "CMD_3") (pintype "passive"))
      (node (ref "U2") (pin "24") (pinfunction "GPIO4_24") (pintype "passive"))
    )
    (net (code "41") (name "/SD_SCK") (class "Default")
      (node (ref "J1") (pin "5") (pinfunction "CLK_5") (pintype "passive"))
      (node (ref "U2") (pin "35") (pinfunction "GPIO18_35") (pintype "passive"))
    )
    (net (code "42") (name "/SELECT") (class "Default")
      (node (ref "R13") (pin "1") (pinfunction "1_1") (pintype "passive"))
      (node (ref "SELECT1") (pin "1") (pinfunction "1_1") (pintype "passive"))
      (node (ref "U1") (pin "12") (pinfunction "P6_12") (pintype "passive"))
    )
    (net (code "43") (name "/SHD{slash}SD2") (class "Default")
      (node (ref "IC1") (pin "7") (pinfunction "~{HOLD}_7") (pintype "passive"))
      (node (ref "U2") (pin "28") (pinfunction "SD_DATA_2_28") (pintype "passive"))
      (node (ref "U3") (pin "7") (pinfunction "SIO3_7") (pintype "passive"))
    )
    (net (code "44") (name "/SRAM_CLK") (class "Default")
      (node (ref "R11") (pin "2") (pinfunction "2_2") (pintype "passive"))
      (node (ref "U3") (pin "6") (pinfunction "SCLK_6") (pintype "passive"))
    )
    (net (code "45") (name "/START") (class "Default")
      (node (ref "R10") (pin "1") (pinfunction "1_1") (pintype "passive"))
      (node (ref "START1") (pin "1") (pinfunction "1_1") (pintype "passive"))
      (node (ref "U1") (pin "13") (pinfunction "P7_13") (pintype "passive"))
    )
    (net (code "46") (name "/SWP{slash}SD3") (class "Default")
      (node (ref "IC1") (pin "3") (pinfunction "~{WP}_3") (pintype "passive"))
      (node (ref "U2") (pin "29") (pinfunction "SD_DATA_3_29") (pintype "passive"))
      (node (ref "U3") (pin "3") (pinfunction "SIO2_3") (pintype "passive"))
    )
    (net (code "47") (name "/U0RXD") (class "Default")
      (node (ref "U2") (pin "40") (pinfunction "U0RXD_40") (pintype "passive"))
      (node (ref "U6") (pin "21") (pinfunction "TXD_21") (pintype "passive"))
    )
    (net (code "48") (name "/U0TXD") (class "Default")
      (node (ref "R7") (pin "2") (pinfunction "2_2") (pintype "passive"))
      (node (ref "U6") (pin "20") (pinfunction "RXD_20") (pintype "passive"))
    )
    (net (code "49") (name "/UP") (class "Default")
      (node (ref "R6") (pin "1") (pinfunction "1_1") (pintype "passive"))
      (node (ref "U1") (pin "5") (pinfunction "P0_5") (pintype "passive"))
      (node (ref "UP1") (pin "1") (pinfunction "1_1") (pintype "passive"))
    )
    (net (code "50") (name "/USB_D+") (class "Default")
      (node (ref "U6") (pin "3") (pinfunction "D+_3") (pintype "passive"))
      (node (ref "USB1") (pin "A6") (pinfunction "D+_A6") (pintype "passive"))
      (node (ref "USB1") (pin "B6") (pinfunction "D+_B6") (pintype "passive"))
    )
    (net (code "51") (name "/USB_D-") (class "Default")
      (node (ref "U6") (pin "4") (pinfunction "D-_4") (pintype "passive"))
      (node (ref "USB1") (pin "A7") (pinfunction "D-_A7") (pintype "passive"))
      (node (ref "USB1") (pin "B7") (pinfunction "D-_B7") (pintype "passive"))
    )
    (net (code "52") (name "/USB_DET") (class "Default")
      (node (ref "R28") (pin "2") (pinfunction "2_2") (pintype "passive"))
      (node (ref "R30") (pin "1") (pinfunction "1_1") (pintype "passive"))
      (node (ref "U2") (pin "10") (pinfunction "VDET_1_10") (pintype "passive"))
    )
    (net (code "53") (name "/VBAT_S") (class "Default")
      (node (ref "C17") (pin "2") (pinfunction "2_2") (pintype "passive"))
      (node (ref "C41") (pin "2") (pinfunction "2_2") (pintype "passive"))
      (node (ref "R40") (pin "2") (pinfunction "2_2") (pintype "passive"))
      (node (ref "R41") (pin "1") (pinfunction "1_1") (pintype "passive"))
      (node (ref "U2") (pin "8") (pinfunction "SENSOR_VN_8") (pintype "passive"))
    )
    (net (code "54") (name "/XTAL_N") (class "Default")
      (node (ref "C1") (pin "1") (pinfunction "1_1") (pintype "passive"))
      (node (ref "U2") (pin "44") (pinfunction "XTAL_N_44") (pintype "passive"))
      (node (ref "X1") (pin "3") (pinfunction "3_3") (pintype "passive"))
    )
    (net (code "55") (name "/XTAL_P") (class "Default")
      (node (ref "R3") (pin "1") (pinfunction "1_1") (pintype "passive"))
      (node (ref "U2") (pin "45") (pinfunction "XTAL_P_45") (pintype "passive"))
    )
    (net (code "56") (name "AGND") (class "Default")
      (node (ref "C22") (pin "2") (pinfunction "2_2") (pintype "passive"))
      (node (ref "C23") (pin "2") (pinfunction "2_2") (pintype "passive"))
      (node (ref "C24") (pin "1") (pinfunction "1_1") (pintype "passive"))
      (node (ref "C26") (pin "1") (pinfunction "1_1") (pintype "passive"))
      (node (ref "C35") (pin "1") (pinfunction "1_1") (pintype "passive"))
      (node (ref "C39") (pin "1") (pinfunction "1_1") (pintype "passive"))
      (node (ref "C40") (pin "1") (pinfunction "1_1") (pintype "passive"))
      (node (ref "R33") (pin "2") (pinfunction "2_2") (pintype "passive"))
      (node (ref "U4") (pin "28") (pinfunction "AGND_28") (pintype "passive"))
    )
    (net (code "57") (name "GND") (class "Default")
      (node (ref "A1") (pin "2") (pinfunction "2_2") (pintype "passive"))
      (node (ref "B1") (pin "2") (pinfunction "2_2") (pintype "passive"))
      (node (ref "BT1") (pin "2") (pintype "passive"))
      (node (ref "C1") (pin "2") (pinfunction "2_2") (pintype "passive"))
      (node (ref "C10") (pin "1") (pinfunction "1_1") (pintype "passive"))
      (node (ref "C11") (pin "1") (pinfunction "1_1") (pintype "passive"))
      (node (ref "C12") (pin "1") (pinfunction "1_1") (pintype "passive"))
      (node (ref "C13") (pin "1") (pinfunction "1_1") (pintype "passive"))
      (node (ref "C14") (pin "1") (pinfunction "1_1") (pintype "passive"))
      (node (ref "C15") (pin "1") (pinfunction "1_1") (pintype "passive"))
      (node (ref "C18") (pin "1") (pinfunction "1_1") (pintype "passive"))
      (node (ref "C19") (pin "1") (pinfunction "1_1") (pintype "passive"))
      (node (ref "C2") (pin "2") (pinfunction "2_2") (pintype "passive"))
      (node (ref "C20") (pin "1") (pinfunction "1_1") (pintype "passive"))
      (node (ref "C21") (pin "1") (pinfunction "1_1") (pintype "passive"))
      (node (ref "C25") (pin "1") (pinfunction "1_1") (pintype "passive"))
      (node (ref "C27") (pin "1") (pinfunction "1_1") (pintype "passive"))
      (node (ref "C28") (pin "1") (pinfunction "1_1") (pintype "passive"))
      (node (ref "C3") (pin "1") (pinfunction "1_1") (pintype "passive"))
      (node (ref "C31") (pin "1") (pinfunction "1_1") (pintype "passive"))
      (node (ref "C32") (pin "1") (pinfunction "1_1") (pintype "passive"))
      (node (ref "C33") (pin "1") (pinfunction "1_1") (pintype "passive"))
      (node (ref "C36") (pin "1") (pinfunction "1_1") (pintype "passive"))
      (node (ref "C37") (pin "1") (pinfunction "1_1") (pintype "passive"))
      (node (ref "C38") (pin "1") (pinfunction "1_1") (pintype "passive"))
      (node (ref "C4") (pin "2") (pinfunction "2_2") (pintype "passive"))
      (node (ref "C41") (pin "1") (pinfunction "1_1") (pintype "passive"))
      (node (ref "C42") (pin "1") (pinfunction "1_1") (pintype "passive"))
      (node (ref "C43") (pin "1") (pinfunction "1_1") (pintype "passive"))
      (node (ref "C5") (pin "1") (pinfunction "1_1") (pintype "passive"))
      (node (ref "C58") (pin "1") (pinfunction "1_1") (pintype "passive"))
      (node (ref "C6") (pin "1") (pinfunction "1_1") (pintype "passive"))
      (node (ref "C8") (pin "1") (pinfunction "1_1") (pintype "passive"))
      (node (ref "C9") (pin "1") (pinfunction "1_1") (pintype "passive"))
      (node (ref "CON1") (pin "6") (pinfunction "6_6") (pintype "passive"))
      (node (ref "D1") (pin "2") (pinfunction "K_2") (pintype "passive"))
      (node (ref "DOWN1") (pin "2") (pinfunction "2_2") (pintype "passive"))
      (node (ref "IC1") (pin "4") (pinfunction "GND_4") (pintype "passive"))
      (node (ref "J1") (pin "0") (pinfunction "GND_0") (pintype "passive"))
      (node (ref "J1") (pin "6") (pinfunction "VSS_6") (pintype "passive"))
      (node (ref "JP1") (pin "2") (pinfunction "ANT_2") (pintype "passive"))
      (node (ref "LEFT1") (pin "2") (pinfunction "2_2") (pintype "passive"))
      (node (ref "MENU1") (pin "2") (pinfunction "2_2") (pintype "passive"))
      (node (ref "Q2") (pin "2") (pinfunction "E_2") (pintype "passive"))
      (node (ref "R22") (pin "2") (pinfunction "2_2") (pintype "passive"))
      (node (ref "R23") (pin "2") (pinfunction "2_2") (pintype "passive"))
      (node (ref "R30") (pin "2") (pinfunction "2_2") (pintype "passive"))
      (node (ref "R31") (pin "1") (pinfunction "1_1") (pintype "passive"))
      (node (ref "R32") (pin "1") (pinfunction "1_1") (pintype "passive"))
      (node (ref "R33") (pin "1") (pinfunction "1_1") (pintype "passive"))
      (node (ref "R37") (pin "2") (pinfunction "2_2") (pintype "passive"))
      (node (ref "R39") (pin "1") (pinfunction "1_1") (pintype "passive"))
      (node (ref "R41") (pin "2") (pinfunction "2_2") (pintype "passive"))
      (node (ref "RIGHT1") (pin "2") (pinfunction "2_2") (pintype "passive"))
      (node (ref "SELECT1") (pin "2") (pinfunction "2_2") (pintype "passive"))
      (node (ref "START1") (pin "2") (pinfunction "2_2") (pintype "passive"))
      (node (ref "U1") (pin "17") (pinfunction "GND_17") (pintype "passive"))
      (node (ref "U1") (pin "2") (pinfunction "A0_2") (pintype "passive"))
      (node (ref "U1") (pin "3") (pinfunction "A1_3") (pintype "passive"))
      (node (ref "U1") (pin "4") (pinfunction "A2_4") (pintype "passive"))
      (node (ref "U1") (pin "9") (pinfunction "GND_9") (pintype "passive"))
      (node (ref "U10") (pin "2") (pinfunction "GND_2") (pintype "passive"))
      (node (ref "U2") (pin "49") (pinfunction "GND_49") (pintype "passive"))
      (node (ref "U3") (pin "4") (pinfunction "VSS_4") (pintype "passive"))
      (node (ref "U4") (pin "12") (pinfunction "DGND_12") (pintype "passive"))
      (node (ref "U4") (pin "24") (pinfunction "SPKGND_24") (pintype "passive"))
      (node (ref "U4") (pin "33") (pinfunction "GND_33") (pintype "passive"))
      (node (ref "U5") (pin "5") (pinfunction "GND_5") (pintype "passive"))
      (node (ref "U5") (pin "6") (pinfunction "GND_6") (pintype "passive"))
      (node (ref "U5") (pin "9") (pinfunction "GND_9") (pintype "passive"))
      (node (ref "U6") (pin "2") (pinfunction "GND_2") (pintype "passive"))
      (node (ref "U6") (pin "25") (pinfunction "GND_25") (pintype "passive"))
      (node (ref "U8") (pin "2") (pinfunction "GND_2") (pintype "passive"))
      (node (ref "U9") (pin "1") (pinfunction "GND_1") (pintype "passive"))
      (node (ref "U9") (pin "12") (pinfunction "GND4_12") (pintype "passive"))
      (node (ref "U9") (pin "5") (pinfunction "GND2_5") (pintype "passive"))
      (node (ref "U9") (pin "6") (pinfunction "GND3_6") (pintype "passive"))
      (node (ref "UP1") (pin "2") (pinfunction "2_2") (pintype "passive"))
      (node (ref "USB1") (pin "A1") (pinfunction "GND_A1") (pintype "passive"))
      (node (ref "USB1") (pin "A12") (pinfunction "GND_A12") (pintype "passive"))
      (node (ref "USB1") (pin "B1") (pinfunction "GND_B1") (pintype "passive"))
      (node (ref "USB1") (pin "B12") (pinfunction "GND_B12") (pintype "passive"))
      (node (ref "X1") (pin "2") (pinfunction "2_2") (pintype "passive"))
      (node (ref "X1") (pin "4") (pinfunction "4_4") (pintype "passive"))
    )
    (net (code "58") (name "Net-(C2-Pad1)") (class "Default")
      (node (ref "C2") (pin "1") (pinfunction "1_1") (pintype "passive"))
      (node (ref "R3") (pin "2") (pinfunction "2_2") (pintype "passive"))
      (node (ref "X1") (pin "1") (pinfunction "1_1") (pintype "passive"))
    )
    (net (code "59") (name "Net-(C12-Pad2)") (class "Default")
      (node (ref "C12") (pin "2") (pinfunction "2_2") (pintype "passive"))
      (node (ref "L1") (pin "2") (pinfunction "2_2") (pintype "passive"))
      (node (ref "U2") (pin "3") (pinfunction "VDD3P3_3") (pintype "passive"))
      (node (ref "U2") (pin "4") (pinfunction "VDD3P3_4") (pintype "passive"))
    )
    (net (code "60") (name "Net-(C13-Pad2)") (class "Default")
      (node (ref "C13") (pin "2") (pinfunction "2_2") (pintype "passive"))
      (node (ref "JP1") (pin "1") (pinfunction "ANT_1") (pintype "passive"))
      (node (ref "L2") (pin "1") (pinfunction "1_1") (pintype "passive"))
    )
    (net (code "61") (name "Net-(CON1-Pad2)") (class "Default")
      (node (ref "CON1") (pin "2") (pinfunction "2_2") (pintype "passive"))
      (node (ref "R27") (pin "2") (pinfunction "2_2") (pintype "passive"))
      (node (ref "R29") (pin "1") (pinfunction "1_1") (pintype "passive"))
    )
    (net (code "62") (name "Net-(Q2-B)") (class "Default")
      (node (ref "Q2") (pin "1") (pinfunction "B_1") (pintype "passive"))
      (node (ref "R36") (pin "2") (pinfunction "2_2") (pintype "passive"))
      (node (ref "R38") (pin "2") (pinfunction "2_2") (pintype "passive"))
    )
    (net (code "63") (name "Net-(Q2-C)") (class "Default")
      (node (ref "Q2") (pin "3") (pinfunction "C_3") (pintype "passive"))
      (node (ref "R35") (pin "1") (pinfunction "1_1") (pintype "passive"))
    )
    (net (code "64") (name "Net-(U2-CAP1)") (class "Default")
      (node (ref "C5") (pin "2") (pinfunction "2_2") (pintype "passive"))
      (node (ref "C7") (pin "2") (pinfunction "2_2") (pintype "passive"))
      (node (ref "R4") (pin "2") (pinfunction "2_2") (pintype "passive"))
      (node (ref "U2") (pin "48") (pinfunction "CAP1_48") (pintype "passive"))
    )
    (net (code "65") (name "Net-(U2-CAP2)") (class "Default")
      (node (ref "C7") (pin "1") (pinfunction "1_1") (pintype "passive"))
      (node (ref "R4") (pin "1") (pinfunction "1_1") (pintype "passive"))
      (node (ref "U2") (pin "47") (pinfunction "CAP2_47") (pintype "passive"))
    )
    (net (code "66") (name "Net-(U2-LNA_IN)") (class "Default")
      (node (ref "C14") (pin "2") (pinfunction "2_2") (pintype "passive"))
      (node (ref "L2") (pin "2") (pinfunction "2_2") (pintype "passive"))
      (node (ref "U2") (pin "2") (pinfunction "LNA_IN_2") (pintype "passive"))
    )
    (net (code "67") (name "Net-(U2-SENSOR_CAPN)") (class "Default")
      (node (ref "C17") (pin "1") (pinfunction "1_1") (pintype "passive"))
      (node (ref "U2") (pin "7") (pinfunction "SENSOR_CAPN_7") (pintype "passive"))
    )
    (net (code "68") (name "Net-(U2-SENSOR_CAPP)") (class "Default")
      (node (ref "C16") (pin "2") (pinfunction "2_2") (pintype "passive"))
      (node (ref "U2") (pin "6") (pinfunction "SENSOR_CAPP_6") (pintype "passive"))
    )
    (net (code "69") (name "Net-(U2-U0TXD)") (class "Default")
      (node (ref "R7") (pin "1") (pinfunction "1_1") (pintype "passive"))
      (node (ref "U2") (pin "41") (pinfunction "U0TXD_41") (pintype "passive"))
    )
    (net (code "70") (name "Net-(U4-DBVDD)") (class "Default")
      (node (ref "C27") (pin "2") (pinfunction "2_2") (pintype "passive"))
      (node (ref "C28") (pin "2") (pinfunction "2_2") (pintype "passive"))
      (node (ref "R24") (pin "2") (pinfunction "2_2") (pintype "passive"))
      (node (ref "U4") (pin "13") (pinfunction "DCVDD_13") (pintype "passive"))
      (node (ref "U4") (pin "14") (pinfunction "DBVDD_14") (pintype "passive"))
    )
    (net (code "71") (name "Net-(U4-L2{slash}GPIO2)") (class "Default")
      (node (ref "C29") (pin "1") (pinfunction "1_1") (pintype "passive"))
      (node (ref "U4") (pin "3") (pinfunction "L2/GPIO2_3") (pintype "passive"))
    )
    (net (code "72") (name "Net-(U4-LOUT2)") (class "Default")
      (node (ref "B2") (pin "2") (pinfunction "2_2") (pintype "passive"))
      (node (ref "U4") (pin "25") (pinfunction "LOUT2_25") (pintype "passive"))
    )
    (net (code "73") (name "Net-(U4-MODE)") (class "Default")
      (node (ref "R31") (pin "2") (pinfunction "2_2") (pintype "passive"))
      (node (ref "U4") (pin "18") (pinfunction "MODE_18") (pintype "passive"))
    )
    (net (code "74") (name "Net-(U4-R2{slash}GPIO3)") (class "Default")
      (node (ref "C30") (pin "1") (pinfunction "1_1") (pintype "passive"))
      (node (ref "U4") (pin "6") (pinfunction "R2/GPIO3_6") (pintype "passive"))
    )
    (net (code "75") (name "Net-(U4-ROUT2)") (class "Default")
      (node (ref "B2") (pin "1") (pinfunction "1_1") (pintype "passive"))
      (node (ref "U4") (pin "23") (pinfunction "ROUT2_23") (pintype "passive"))
    )
    (net (code "76") (name "Net-(U4-SPKVDD)") (class "Default")
      (node (ref "C22") (pin "1") (pinfunction "1_1") (pintype "passive"))
      (node (ref "C23") (pin "1") (pinfunction "1_1") (pintype "passive"))
      (node (ref "R21") (pin "2") (pinfunction "2_2") (pintype "passive"))
      (node (ref "U4") (pin "26") (pinfunction "SPKVDD_26") (pintype "passive"))
    )
    (net (code "77") (name "Net-(U4-VMID)") (class "Default")
      (node (ref "C35") (pin "2") (pinfunction "2_2") (pintype "passive"))
      (node (ref "U4") (pin "27") (pinfunction "VMID_27") (pintype "passive"))
    )
    (net (code "78") (name "Net-(U5-L{slash}R)") (class "Default")
      (node (ref "R23") (pin "1") (pinfunction "1_1") (pintype "passive"))
      (node (ref "U5") (pin "4") (pinfunction "L/R_4") (pintype "passive"))
    )
    (net (code "79") (name "Net-(U6-~{RS}T)") (class "Default")
      (node (ref "R25") (pin "1") (pinfunction "1_1") (pintype "passive"))
      (node (ref "U6") (pin "9") (pinfunction "~{RS}T_9") (pintype "passive"))
    )
    (net (code "80") (name "Net-(U8-FB)") (class "Default")
      (node (ref "R34") (pin "2") (pinfunction "2_2") (pintype "passive"))
      (node (ref "R39") (pin "2") (pinfunction "2_2") (pintype "passive"))
      (node (ref "U8") (pin "5") (pinfunction "FB_5") (pintype "passive"))
    )
    (net (code "81") (name "Net-(U8-SW)") (class "Default")
      (node (ref "L3") (pin "1") (pinfunction "1_1") (pintype "passive"))
      (node (ref "U8") (pin "3") (pinfunction "SW_3") (pintype "passive"))
    )
    (net (code "82") (name "Net-(U9-LEDK)") (class "Default")
      (node (ref "R35") (pin "2") (pinfunction "2_2") (pintype "passive"))
      (node (ref "U9") (pin "2") (pinfunction "LEDK_2") (pintype "passive"))
    )
    (net (code "83") (name "Net-(U10-PROG)") (class "Default")
      (node (ref "R37") (pin "1") (pinfunction "1_1") (pintype "passive"))
      (node (ref "U10") (pin "5") (pinfunction "PROG_5") (pintype "passive"))
    )
    (net (code "84") (name "VBAT") (class "Default")
      (node (ref "BT1") (pin "1") (pintype "passive"))
      (node (ref "C43") (pin "2") (pinfunction "2_2") (pintype "passive"))
      (node (ref "Q1") (pin "3") (pinfunction "D_3") (pintype "passive"))
      (node (ref "R40") (pin "1") (pinfunction "1_1") (pintype "passive"))
      (node (ref "U10") (pin "3") (pinfunction "BAT_3") (pintype "passive"))
    )
    (net (code "85") (name "VBUS") (class "Default")
      (node (ref "C42") (pin "2") (pinfunction "2_2") (pintype "passive"))
      (node (ref "Q1") (pin "1") (pinfunction "G_1") (pintype "passive"))
      (node (ref "R28") (pin "1") (pinfunction "1_1") (pintype "passive"))
      (node (ref "R32") (pin "2") (pinfunction "2_2") (pintype "passive"))
      (node (ref "U10") (pin "4") (pinfunction "VCC_4") (pintype "passive"))
      (node (ref "U6") (pin "8") (pinfunction "VBUS_8") (pintype "passive"))
      (node (ref "USB1") (pin "A4") (pinfunction "VBUS_A4") (pintype "passive"))
      (node (ref "USB1") (pin "A9") (pinfunction "VBUS_A9") (pintype "passive"))
      (node (ref "USB1") (pin "B4") (pinfunction "VBUS_B4") (pintype "passive"))
      (node (ref "USB1") (pin "B9") (pinfunction "VBUS_B9") (pintype "passive"))
      (node (ref "VD1") (pin "1") (pinfunction "A_1") (pintype "passive"))
    )
    (net (code "86") (name "VCC") (class "Default")
      (node (ref "C36") (pin "2") (pinfunction "2_2") (pintype "passive"))
      (node (ref "Q1") (pin "2") (pinfunction "S_2") (pintype "passive"))
      (node (ref "U8") (pin "1") (pinfunction "EN_1") (pintype "passive"))
      (node (ref "U8") (pin "4") (pinfunction "VIN_4") (pintype "passive"))
      (node (ref "VD1") (pin "2") (pinfunction "K_2") (pintype "passive"))
    )
    (net (code "87") (name "VDD_SDIO") (class "Default")
      (node (ref "C20") (pin "2") (pinfunction "2_2") (pintype "passive"))
      (node (ref "IC1") (pin "8") (pinfunction "VCC_8") (pintype "passive"))
      (node (ref "R19") (pin "2") (pinfunction "2_2") (pintype "passive"))
      (node (ref "U2") (pin "26") (pinfunction "VDD_SDIO_26") (pintype "passive"))
      (node (ref "U3") (pin "8") (pinfunction "VDD_8") (pintype "passive"))
    )
    (net (code "88") (name "unconnected-(CON1-Pad1)") (class "Default")
      (node (ref "CON1") (pin "1") (pinfunction "1_1") (pintype "passive"))
    )
    (net (code "89") (name "unconnected-(CON1-Pad3)") (class "Default")
      (node (ref "CON1") (pin "3") (pinfunction "3_3") (pintype "passive"))
    )
    (net (code "90") (name "unconnected-(CON1-Pad4)") (class "Default")
      (node (ref "CON1") (pin "4") (pinfunction "4_4") (pintype "passive"))
    )
    (net (code "91") (name "unconnected-(CON1-Pad7)") (class "Default")
      (node (ref "CON1") (pin "7") (pinfunction "7_7") (pintype "passive"))
    )
    (net (code "92") (name "unconnected-(J1-DATA1-Pad8)") (class "Default")
      (node (ref "J1") (pin "8") (pinfunction "DATA1_8") (pintype "passive+no_connect"))
    )
    (net (code "93") (name "unconnected-(J1-DATA2-Pad1)") (class "Default")
      (node (ref "J1") (pin "1") (pinfunction "DATA2_1") (pintype "passive+no_connect"))
    )
    (net (code "94") (name "unconnected-(U1-~{INIT}-Pad14)") (class "Default")
      (node (ref "U1") (pin "14") (pinfunction "~{INIT}_14") (pintype "passive"))
    )
    (net (code "95") (name "unconnected-(U4-ADCDAT-Pad9)") (class "Default")
      (node (ref "U4") (pin "9") (pinfunction "ADCDAT_9") (pintype "passive+no_connect"))
    )
    (net (code "96") (name "unconnected-(U4-AUXL-Pad19)") (class "Default")
      (node (ref "U4") (pin "19") (pinfunction "AUXL_19") (pintype "passive+no_connect"))
    )
    (net (code "97") (name "unconnected-(U4-AUXR-Pad20)") (class "Default")
      (node (ref "U4") (pin "20") (pinfunction "AUXR_20") (pintype "passive+no_connect"))
    )
    (net (code "98") (name "unconnected-(U4-LIN-Pad2)") (class "Default")
      (node (ref "U4") (pin "2") (pinfunction "LIN_2") (pintype "passive+no_connect"))
    )
    (net (code "99") (name "unconnected-(U4-LIP-Pad1)") (class "Default")
      (node (ref "U4") (pin "1") (pinfunction "LIP_1") (pintype "passive+no_connect"))
    )
    (net (code "100") (name "unconnected-(U4-LOUT1-Pad30)") (class "Default")
      (node (ref "U4") (pin "30") (pinfunction "LOUT1_30") (pintype "passive+no_connect"))
    )
    (net (code "101") (name "unconnected-(U4-MICBIAS-Pad32)") (class "Default")
      (node (ref "U4") (pin "32") (pinfunction "MICBIAS_32") (pintype "passive+no_connect"))
    )
    (net (code "102") (name "unconnected-(U4-OUT3-Pad22)") (class "Default")
      (node (ref "U4") (pin "22") (pinfunction "OUT3_22") (pintype "passive+no_connect"))
    )
    (net (code "103") (name "unconnected-(U4-OUT4-Pad21)") (class "Default")
      (node (ref "U4") (pin "21") (pinfunction "OUT4_21") (pintype "passive+no_connect"))
    )
    (net (code "104") (name "unconnected-(U4-RIN-Pad5)") (class "Default")
      (node (ref "U4") (pin "5") (pinfunction "RIN_5") (pintype "passive+no_connect"))
    )
    (net (code "105") (name "unconnected-(U4-RIP-Pad4)") (class "Default")
      (node (ref "U4") (pin "4") (pinfunction "RIP_4") (pintype "passive+no_connect"))
    )
    (net (code "106") (name "unconnected-(U4-ROUT1-Pad29)") (class "Default")
      (node (ref "U4") (pin "29") (pinfunction "ROUT1_29") (pintype "passive+no_connect"))
    )
    (net (code "107") (name "unconnected-(U6-CTS-Pad18)") (class "Default")
      (node (ref "U6") (pin "18") (pinfunction "CTS_18") (pintype "passive"))
    )
    (net (code "108") (name "unconnected-(U6-DCD-Pad24)") (class "Default")
      (node (ref "U6") (pin "24") (pinfunction "DCD_24") (pintype "passive"))
    )
    (net (code "109") (name "unconnected-(U6-DSR-Pad22)") (class "Default")
      (node (ref "U6") (pin "22") (pinfunction "DSR_22") (pintype "passive"))
    )
    (net (code "110") (name "unconnected-(U6-GPIO.0-Pad14)") (class "Default")
      (node (ref "U6") (pin "14") (pinfunction "GPIO.0_14") (pintype "passive"))
    )
    (net (code "111") (name "unconnected-(U6-GPIO.1-Pad13)") (class "Default")
      (node (ref "U6") (pin "13") (pinfunction "GPIO.1_13") (pintype "passive"))
    )
    (net (code "112") (name "unconnected-(U6-GPIO.2-Pad12)") (class "Default")
      (node (ref "U6") (pin "12") (pinfunction "GPIO.2_12") (pintype "passive"))
    )
    (net (code "113") (name "unconnected-(U6-GPIO.3-Pad11)") (class "Default")
      (node (ref "U6") (pin "11") (pinfunction "GPIO.3_11") (pintype "passive"))
    )
    (net (code "114") (name "unconnected-(U6-NC-Pad10)") (class "Default")
      (node (ref "U6") (pin "10") (pinfunction "NC_10") (pintype "passive"))
    )
    (net (code "115") (name "unconnected-(U6-RI-Pad1)") (class "Default")
      (node (ref "U6") (pin "1") (pinfunction "RI_1") (pintype "passive"))
    )
    (net (code "116") (name "unconnected-(U6-SUSPEND-Pad15)") (class "Default")
      (node (ref "U6") (pin "15") (pinfunction "SUSPEND_15") (pintype "passive"))
    )
    (net (code "117") (name "unconnected-(U6-VPP-Pad16)") (class "Default")
      (node (ref "U6") (pin "16") (pinfunction "VPP_16") (pintype "passive"))
    )
    (net (code "118") (name "unconnected-(U6-~{SUSPEN}D-Pad17)") (class "Default")
      (node (ref "U6") (pin "17") (pinfunction "~{SUSPEN}D_17") (pintype "passive"))
    )
    (net (code "119") (name "unconnected-(USB1-CC1-PadA5)") (class "Default")
      (node (ref "USB1") (pin "A5") (pinfunction "CC1_A5") (pintype "passive"))
    )
    (net (code "120") (name "unconnected-(USB1-CC2-PadB5)") (class "Default")
      (node (ref "USB1") (pin "B5") (pinfunction "CC2_B5") (pintype "passive"))
    )
    (net (code "121") (name "unconnected-(USB1-SUB1-PadA8)") (class "Default")
      (node (ref "USB1") (pin "A8") (pinfunction "SUB1_A8") (pintype "passive"))
    )
    (net (code "122") (name "unconnected-(USB1-SUB2-PadB8)") (class "Default")
      (node (ref "USB1") (pin "B8") (pinfunction "SUB2_B8") (pintype "passive"))
    )
  )
)
